# DSDPLC_MCU.net
KiCad netlist of a schematic drawn in Altium Designer
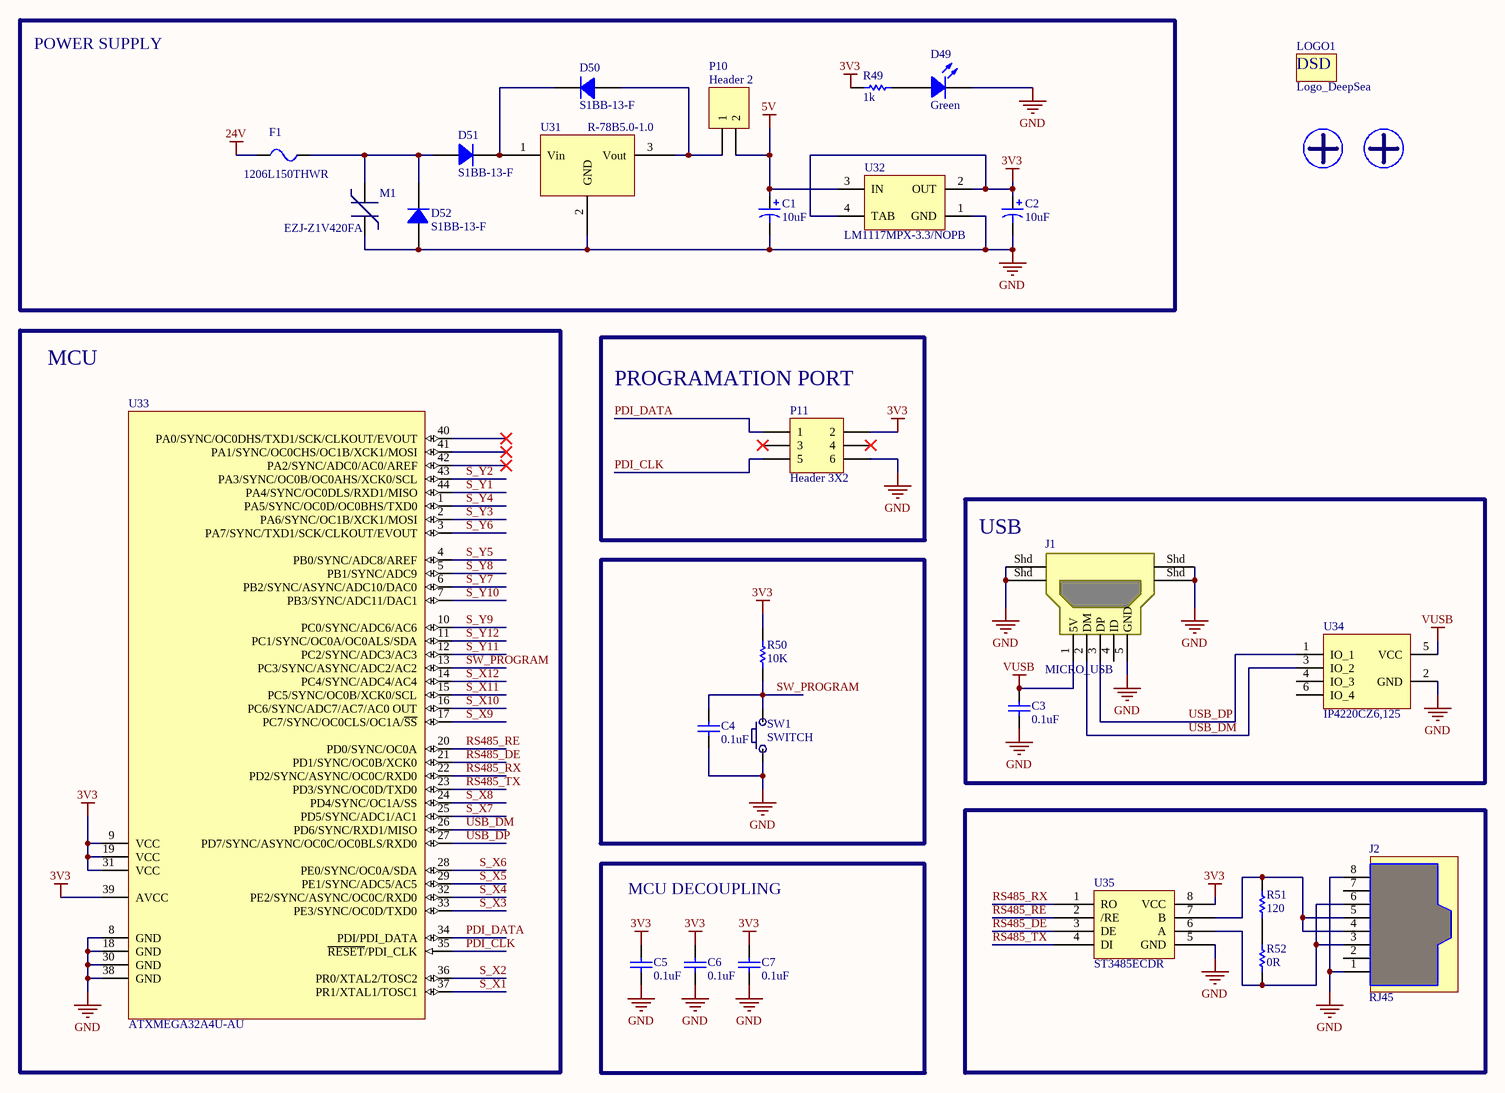
[diagram p0: DSDPLC_MCU.SchDoc]

(export (version "E")
  (design (tool "Eeschema 10.0.6"))
  (components
    (comp (ref "C1") (value "10uF") (footprint "C_TANT_A_3216_N") (libsource (lib "General") (part "CP_SMD")))
    (comp (ref "C2") (value "10uF") (footprint "C_TANT_A_3216_N") (libsource (lib "General") (part "CP_SMD")))
    (comp (ref "C3") (value "0.1uF") (footprint "C0603_N") (libsource (lib "General") (part "C_SMD")))
    (comp (ref "C4") (value "0.1uF") (footprint "C0603_N") (libsource (lib "General") (part "C_SMD")))
    (comp (ref "C5") (value "0.1uF") (footprint "C0603_N") (libsource (lib "General") (part "C_SMD")))
    (comp (ref "C6") (value "0.1uF") (footprint "C0603_N") (libsource (lib "General") (part "C_SMD")))
    (comp (ref "C7") (value "0.1uF") (footprint "C0603_N") (libsource (lib "General") (part "C_SMD")))
    (comp (ref "D49")
      (value "Green")
      (footprint "R0603_N")
      (fields (field (name "COLOR") "Green"))
      (libsource (lib "General") (part "LED_SMD"))
    )
    (comp (ref "D50")
      (value "S1BB-13-F")
      (footprint "SMB_N")
      (description "DIODE GEN PURPOSE 100V 1A SMB")
      (fields (field (name "MANUFACTURER") "Diodes Incorporated"))
      (libsource (lib "General") (part "S1BB-13-F"))
    )
    (comp (ref "D51")
      (value "S1BB-13-F")
      (footprint "SMB_N")
      (description "DIODE GEN PURPOSE 100V 1A SMB")
      (fields (field (name "MANUFACTURER") "Diodes Incorporated"))
      (libsource (lib "General") (part "S1BB-13-F"))
    )
    (comp (ref "D52")
      (value "S1BB-13-F")
      (footprint "SMB_N")
      (description "DIODE GEN PURPOSE 100V 1A SMB")
      (fields (field (name "MANUFACTURER") "Diodes Incorporated"))
      (libsource (lib "General") (part "S1BB-13-F"))
    )
    (comp (ref "F1")
      (value "1206L150THWR")
      (footprint "R1206_N")
      (description "FUSE PTC RESET 8V 1.50A 1206")
      (fields (field (name "MANUFACTURER") "Littelfuse Inc"))
      (libsource (lib "General") (part "1206L150THWR"))
    )
    (comp (ref "J1")
      (value "MICRO_USB")
      (footprint "USB_MICRO_SMD")
      (description "CONN USB MICRO B RECPT SMT R/A")
      (fields (field (name "MANUFACTURER") "FCI") (field (name "MANUFACTURER PART NUMBER") "10118194-0001LF"))
      (libsource (lib "General") (part "MICRO_USB"))
    )
    (comp (ref "J2")
      (value "RJ45")
      (footprint "rj45")
      (description "CONN MOD JACK R/A 8P8C SHIELDED")
      (fields
        (field (name "MANUFACTURER") "TE Connectivity")
        (field (name "MANUFACTURER PART NUMBER") "5555153-1")
      )
      (libsource (lib "General") (part "RJ45"))
    )
    (comp (ref "LOGO1")
      (value "Logo_DeepSea")
      (footprint "DeepSea_logo1")
      (libsource (lib "General") (part "Logo_DeepSea"))
    )
    (comp (ref "M1")
      (value "EZJ-Z1V420FA")
      (footprint "R0603_N")
      (description "VARISTOR 42V 15A 0603")
      (fields (field (name "MANUFACTURER") "Panasonic Electronic Components"))
      (libsource (lib "General") (part "EZJ-Z1V420FA"))
    )
    (comp (ref "M2")
      (value "MountingHole-1/8in")
      (footprint "MoutingHole-1/8in")
      (libsource (lib "General") (part "MountingHole-1/8in"))
    )
    (comp (ref "M3")
      (value "MountingHole-1/8in")
      (footprint "MoutingHole-1/8in")
      (libsource (lib "General") (part "MountingHole-1/8in"))
    )
    (comp (ref "P10")
      (value "Header 2")
      (footprint "HDR1X2")
      (description "Header, 2-Pin")
      (fields (field (name "PUBLISHER") "Altium Limited"))
      (libsource (lib "Miscellaneous Connectors") (part "Header 2"))
    )
    (comp (ref "P11")
      (value "Header 3X2")
      (footprint "HDR2X3")
      (description "Header, 3-Pin, Dual row")
      (fields (field (name "PUBLISHER") "Altium Limited"))
      (libsource (lib "Miscellaneous Connectors") (part "Header 3X2"))
    )
    (comp (ref "R49")
      (value "1k")
      (footprint "R0603_N")
      (fields (field (name "Comment") "R_SMD"))
      (libsource (lib "General") (part "R_SMD"))
    )
    (comp (ref "R50") (value "10K") (footprint "R0603_N") (libsource (lib "discrete") (part "R_SMD")))
    (comp (ref "R51") (value "120") (footprint "R0603_N") (libsource (lib "discrete") (part "R_SMD")))
    (comp (ref "R52") (value "0R") (footprint "R0603_N") (libsource (lib "discrete") (part "R_SMD")))
    (comp (ref "SW1")
      (value "SWITCH")
      (footprint "swich_foot")
      (description "SWITCH TACTILE SPST-NO 0.05A 12V")
      (fields
        (field (name "MANUFACTURER") "TE Connectivity")
        (field (name "MANUFACTURER PART NUMBER") "FSM4JSMATR")
      )
      (libsource (lib "General") (part "SWITCH"))
    )
    (comp (ref "U31")
      (value "R-78B5.0-1.0")
      (footprint "SIP3_RECOM")
      (description "CONV DC/DC 1A 5V OUT SIP VERT")
      (fields (field (name "MANUFACTURER") "Recom Power"))
      (libsource (lib "General") (part "R-78B5.0-1.0"))
    )
    (comp (ref "U32")
      (value "LM1117MPX-3.3/NOPB")
      (footprint "MP04A_N")
      (description "800mA Low-Dropout Linear Regulator, 4-pin SOT-223, Pb-Free")
      (fields
        (field (name "MANUFACTURER") "National Semiconductor")
        (field (name "PUBLISHER") "Altium Limited")
      )
      (libsource (lib "NSC LDO") (part "LM1117MPX-3.3/NOPB"))
    )
    (comp (ref "U33")
      (value "ATXMEGA32A4U-AU")
      (footprint "44A_N")
      (description "IC MCU 8BIT 32KB FLASH 44TQFP")
      (fields (field (name "MANUFACTURER") "Atmel"))
      (libsource (lib "General") (part "ATXMEGA32A4U-AU"))
    )
    (comp (ref "U34")
      (value "IP4220CZ6,125")
      (footprint "SOT457_N")
      (description "IC USB DUAL ESD PROTECT 6TSOP")
      (fields (field (name "MANUFACTURER") "NXP Semiconductors"))
      (libsource (lib "General") (part "IP4220CZ6,125"))
    )
    (comp (ref "U35")
      (value "ST3485ECDR")
      (footprint "SOIC8WA_N")
      (description "TXRX RS485/422 3.3V ESD 8-SOIC")
      (fields (field (name "MANUFACTURER") "STMicroelectronics"))
      (libsource (lib "General") (part "ST3485ECDR"))
    )
  )
  (nets
    (net (code "1") (name "/PDI_CLK") (class "Default")
      (node (ref "P11") (pin "5") (pinfunction "5_5") (pintype "passive"))
      (node (ref "U33") (pin "35") (pinfunction "~{RESET}/PDI_CLK_35") (pintype "input"))
    )
    (net (code "2") (name "/PDI_DATA") (class "Default")
      (node (ref "P11") (pin "1") (pinfunction "1_1") (pintype "passive"))
      (node (ref "U33") (pin "34") (pinfunction "PDI/PDI_DATA_34") (pintype "bidirectional"))
    )
    (net (code "3") (name "/RS485_DE") (class "Default")
      (node (ref "U33") (pin "21") (pinfunction "PD1/SYNC/OC0B/XCK0_21") (pintype "bidirectional"))
      (node (ref "U35") (pin "3") (pinfunction "DE_3") (pintype "passive"))
    )
    (net (code "4") (name "/RS485_RE") (class "Default")
      (node (ref "U33") (pin "20") (pinfunction "PD0/SYNC/OC0A_20") (pintype "bidirectional"))
      (node (ref "U35") (pin "2") (pinfunction "/RE_2") (pintype "passive"))
    )
    (net (code "5") (name "/RS485_RX") (class "Default")
      (node (ref "U33") (pin "22") (pinfunction "PD2/SYNC/ASYNC/OC0C/RXD0_22") (pintype "bidirectional"))
      (node (ref "U35") (pin "1") (pinfunction "RO_1") (pintype "passive"))
    )
    (net (code "6") (name "/RS485_TX") (class "Default")
      (node (ref "U33") (pin "23") (pinfunction "PD3/SYNC/OC0D/TXD0_23") (pintype "bidirectional"))
      (node (ref "U35") (pin "4") (pinfunction "DI_4") (pintype "passive"))
    )
    (net (code "7") (name "/SW_PROGRAM") (class "Default")
      (node (ref "C4") (pin "1") (pinfunction "1_1") (pintype "passive"))
      (node (ref "R50") (pin "1") (pinfunction "1_1") (pintype "passive"))
      (node (ref "SW1") (pin "2") (pinfunction "*_2") (pintype "passive"))
      (node (ref "U33") (pin "13") (pinfunction "PC3/SYNC/ASYNC/ADC2/AC2_13") (pintype "bidirectional"))
    )
    (net (code "8") (name "/S_X1") (class "Default")
      (node (ref "U33") (pin "37") (pinfunction "PR1/XTAL1/TOSC1_37") (pintype "bidirectional"))
    )
    (net (code "9") (name "/S_X2") (class "Default")
      (node (ref "U33") (pin "36") (pinfunction "PR0/XTAL2/TOSC2_36") (pintype "bidirectional"))
    )
    (net (code "10") (name "/S_X3") (class "Default")
      (node (ref "U33") (pin "33") (pinfunction "PE3/SYNC/OC0D/TXD0_33") (pintype "bidirectional"))
    )
    (net (code "11") (name "/S_X4") (class "Default")
      (node (ref "U33") (pin "32") (pinfunction "PE2/SYNC/ASYNC/OC0C/RXD0_32") (pintype "bidirectional"))
    )
    (net (code "12") (name "/S_X5") (class "Default")
      (node (ref "U33") (pin "29") (pinfunction "PE1/SYNC/ADC5/AC5_29") (pintype "bidirectional"))
    )
    (net (code "13") (name "/S_X6") (class "Default")
      (node (ref "U33") (pin "28") (pinfunction "PE0/SYNC/OC0A/SDA_28") (pintype "bidirectional"))
    )
    (net (code "14") (name "/S_X7") (class "Default")
      (node (ref "U33") (pin "25") (pinfunction "PD5/SYNC/ADC1/AC1_25") (pintype "bidirectional"))
    )
    (net (code "15") (name "/S_X8") (class "Default")
      (node (ref "U33") (pin "24") (pinfunction "PD4/SYNC/OC1A/SS_24") (pintype "bidirectional"))
    )
    (net (code "16") (name "/S_X9") (class "Default")
      (node (ref "U33") (pin "17") (pinfunction "PC7/SYNC/OC0CLS/OC1A/~{SS}_17") (pintype "bidirectional"))
    )
    (net (code "17") (name "/S_X10") (class "Default")
      (node (ref "U33") (pin "16") (pinfunction "PC6/SYNC/ADC7/AC7/AC0_OUT_16") (pintype "bidirectional"))
    )
    (net (code "18") (name "/S_X11") (class "Default")
      (node (ref "U33") (pin "15") (pinfunction "PC5/SYNC/OC0B/XCK0/SCL_15") (pintype "bidirectional"))
    )
    (net (code "19") (name "/S_X12") (class "Default")
      (node (ref "U33") (pin "14") (pinfunction "PC4/SYNC/ADC4/AC4_14") (pintype "bidirectional"))
    )
    (net (code "20") (name "/S_Y1") (class "Default")
      (node (ref "U33") (pin "44") (pinfunction "PA4/SYNC/OC0DLS/RXD1/MISO_44") (pintype "bidirectional"))
    )
    (net (code "21") (name "/S_Y2") (class "Default")
      (node (ref "U33") (pin "43") (pinfunction "PA3/SYNC/OC0B/OC0AHS/XCK0/SCL_43") (pintype "bidirectional"))
    )
    (net (code "22") (name "/S_Y3") (class "Default")
      (node (ref "U33") (pin "2") (pinfunction "PA6/SYNC/OC1B/XCK1/MOSI_2") (pintype "bidirectional"))
    )
    (net (code "23") (name "/S_Y4") (class "Default")
      (node (ref "U33") (pin "1") (pinfunction "PA5/SYNC/OC0D/OC0BHS/TXD0_1") (pintype "bidirectional"))
    )
    (net (code "24") (name "/S_Y5") (class "Default")
      (node (ref "U33") (pin "4") (pinfunction "PB0/SYNC/ADC8/AREF_4") (pintype "bidirectional"))
    )
    (net (code "25") (name "/S_Y6") (class "Default")
      (node (ref "U33") (pin "3") (pinfunction "PA7/SYNC/TXD1/SCK/CLKOUT/EVOUT_3") (pintype "bidirectional"))
    )
    (net (code "26") (name "/S_Y7") (class "Default")
      (node (ref "U33") (pin "6") (pinfunction "PB2/SYNC/ASYNC/ADC10/DAC0_6") (pintype "bidirectional"))
    )
    (net (code "27") (name "/S_Y8") (class "Default")
      (node (ref "U33") (pin "5") (pinfunction "PB1/SYNC/ADC9_5") (pintype "bidirectional"))
    )
    (net (code "28") (name "/S_Y9") (class "Default")
      (node (ref "U33") (pin "10") (pinfunction "PC0/SYNC/ADC6/AC6_10") (pintype "bidirectional"))
    )
    (net (code "29") (name "/S_Y10") (class "Default")
      (node (ref "U33") (pin "7") (pinfunction "PB3/SYNC/ADC11/DAC1_7") (pintype "bidirectional"))
    )
    (net (code "30") (name "/S_Y11") (class "Default")
      (node (ref "U33") (pin "12") (pinfunction "PC2/SYNC/ADC3/AC3_12") (pintype "bidirectional"))
    )
    (net (code "31") (name "/S_Y12") (class "Default")
      (node (ref "U33") (pin "11") (pinfunction "PC1/SYNC/OC0A/OC0ALS/SDA_11") (pintype "bidirectional"))
    )
    (net (code "32") (name "/USB_DM") (class "Default")
      (node (ref "J1") (pin "2") (pinfunction "DM_2") (pintype "passive"))
      (node (ref "U33") (pin "26") (pinfunction "PD6/SYNC/RXD1/MISO_26") (pintype "bidirectional"))
      (node (ref "U34") (pin "3") (pinfunction "IO_2_3") (pintype "passive"))
    )
    (net (code "33") (name "/USB_DP") (class "Default")
      (node (ref "J1") (pin "3") (pinfunction "DP_3") (pintype "passive"))
      (node (ref "U33") (pin "27") (pinfunction "PD7/SYNC/ASYNC/OC0C/OC0BLS/RXD0_27") (pintype "bidirectional"))
      (node (ref "U34") (pin "1") (pinfunction "IO_1_1") (pintype "passive"))
    )
    (net (code "34") (name "3V3") (class "Default")
      (node (ref "C2") (pin "1") (pinfunction "1_1") (pintype "passive"))
      (node (ref "C5") (pin "2") (pinfunction "2_2") (pintype "passive"))
      (node (ref "C6") (pin "2") (pinfunction "2_2") (pintype "passive"))
      (node (ref "C7") (pin "2") (pinfunction "2_2") (pintype "passive"))
      (node (ref "P11") (pin "2") (pinfunction "2_2") (pintype "passive"))
      (node (ref "R49") (pin "1") (pinfunction "1_1") (pintype "passive"))
      (node (ref "R50") (pin "2") (pinfunction "2_2") (pintype "passive"))
      (node (ref "U32") (pin "2") (pinfunction "OUT_2") (pintype "power_in"))
      (node (ref "U32") (pin "4") (pinfunction "TAB_4") (pintype "power_in"))
      (node (ref "U33") (pin "19") (pinfunction "VCC_19") (pintype "power_in"))
      (node (ref "U33") (pin "31") (pinfunction "VCC_31") (pintype "power_in"))
      (node (ref "U33") (pin "39") (pinfunction "AVCC_39") (pintype "power_in"))
      (node (ref "U33") (pin "9") (pinfunction "VCC_9") (pintype "power_in"))
      (node (ref "U35") (pin "8") (pinfunction "VCC_8") (pintype "passive"))
    )
    (net (code "35") (name "5V") (class "Default")
      (node (ref "C1") (pin "1") (pinfunction "1_1") (pintype "passive"))
      (node (ref "P10") (pin "2") (pinfunction "2_2") (pintype "passive"))
      (node (ref "U32") (pin "3") (pinfunction "IN_3") (pintype "power_in"))
    )
    (net (code "36") (name "24V") (class "Default") (node (ref "F1") (pin "1") (pintype "passive")))
    (net (code "37") (name "GND") (class "Default")
      (node (ref "C1") (pin "2") (pinfunction "2_2") (pintype "passive"))
      (node (ref "C2") (pin "2") (pinfunction "2_2") (pintype "passive"))
      (node (ref "C3") (pin "1") (pinfunction "1_1") (pintype "passive"))
      (node (ref "C4") (pin "2") (pinfunction "2_2") (pintype "passive"))
      (node (ref "C5") (pin "1") (pinfunction "1_1") (pintype "passive"))
      (node (ref "C6") (pin "1") (pinfunction "1_1") (pintype "passive"))
      (node (ref "C7") (pin "1") (pinfunction "1_1") (pintype "passive"))
      (node (ref "D49") (pin "2") (pinfunction "K_2") (pintype "passive"))
      (node (ref "D52") (pin "1") (pinfunction "A_1") (pintype "passive"))
      (node (ref "J1") (pin "5") (pinfunction "GND_5") (pintype "power_in"))
      (node (ref "J1") (pin "Shd") (pinfunction "6_Shd") (pintype "passive"))
      (node (ref "J2") (pin "1") (pintype "passive"))
      (node (ref "J2") (pin "8") (pintype "passive"))
      (node (ref "M1") (pin "2") (pintype "passive"))
      (node (ref "P11") (pin "6") (pinfunction "6_6") (pintype "passive"))
      (node (ref "SW1") (pin "1") (pinfunction "*_1") (pintype "passive"))
      (node (ref "U31") (pin "2") (pinfunction "GND_2") (pintype "passive"))
      (node (ref "U32") (pin "1") (pinfunction "GND_1") (pintype "power_in"))
      (node (ref "U33") (pin "18") (pinfunction "GND_18") (pintype "power_in"))
      (node (ref "U33") (pin "30") (pinfunction "GND_30") (pintype "power_in"))
      (node (ref "U33") (pin "38") (pinfunction "GND_38") (pintype "power_in"))
      (node (ref "U33") (pin "8") (pinfunction "GND_8") (pintype "power_in"))
      (node (ref "U34") (pin "2") (pinfunction "GND_2") (pintype "passive"))
      (node (ref "U35") (pin "5") (pinfunction "GND_5") (pintype "passive"))
    )
    (net (code "38") (name "Net-(D49-A)") (class "Default")
      (node (ref "D49") (pin "1") (pinfunction "A_1") (pintype "passive"))
      (node (ref "R49") (pin "2") (pinfunction "2_2") (pintype "passive"))
    )
    (net (code "39") (name "Net-(D50-A)") (class "Default")
      (node (ref "D50") (pin "1") (pinfunction "A_1") (pintype "passive"))
      (node (ref "P10") (pin "1") (pinfunction "1_1") (pintype "passive"))
      (node (ref "U31") (pin "3") (pinfunction "Vout_3") (pintype "passive"))
    )
    (net (code "40") (name "Net-(D50-K)") (class "Default")
      (node (ref "D50") (pin "2") (pinfunction "K_2") (pintype "passive"))
      (node (ref "D51") (pin "2") (pinfunction "K_2") (pintype "passive"))
      (node (ref "U31") (pin "1") (pinfunction "Vin_1") (pintype "passive"))
    )
    (net (code "41") (name "Net-(D51-A)") (class "Default")
      (node (ref "D51") (pin "1") (pinfunction "A_1") (pintype "passive"))
      (node (ref "D52") (pin "2") (pinfunction "K_2") (pintype "passive"))
      (node (ref "F1") (pin "2") (pintype "passive"))
      (node (ref "M1") (pin "1") (pintype "passive"))
    )
    (net (code "42") (name "Net-(R51-Pad1)") (class "Default")
      (node (ref "R51") (pin "1") (pinfunction "1_1") (pintype "passive"))
      (node (ref "R52") (pin "2") (pinfunction "2_2") (pintype "passive"))
    )
    (net (code "43") (name "Net-(U35-A)") (class "Default")
      (node (ref "J2") (pin "3") (pintype "passive"))
      (node (ref "J2") (pin "6") (pintype "passive"))
      (node (ref "R52") (pin "1") (pinfunction "1_1") (pintype "passive"))
      (node (ref "U35") (pin "6") (pinfunction "A_6") (pintype "passive"))
    )
    (net (code "44") (name "Net-(U35-B)") (class "Default")
      (node (ref "J2") (pin "4") (pintype "passive"))
      (node (ref "J2") (pin "5") (pintype "passive"))
      (node (ref "R51") (pin "2") (pinfunction "2_2") (pintype "passive"))
      (node (ref "U35") (pin "7") (pinfunction "B_7") (pintype "passive"))
    )
    (net (code "45") (name "VUSB") (class "Default")
      (node (ref "C3") (pin "2") (pinfunction "2_2") (pintype "passive"))
      (node (ref "J1") (pin "1") (pinfunction "5V_1") (pintype "power_in"))
      (node (ref "U34") (pin "5") (pinfunction "VCC_5") (pintype "passive"))
    )
    (net (code "46") (name "unconnected-(J1-ID-Pad4)") (class "Default")
      (node (ref "J1") (pin "4") (pinfunction "ID_4") (pintype "passive"))
    )
    (net (code "47") (name "unconnected-(J2-Pad2)") (class "Default")
      (node (ref "J2") (pin "2") (pintype "passive"))
    )
    (net (code "48") (name "unconnected-(J2-Pad7)") (class "Default")
      (node (ref "J2") (pin "7") (pintype "passive"))
    )
    (net (code "49") (name "unconnected-(P11-Pad3)") (class "Default")
      (node (ref "P11") (pin "3") (pinfunction "3_3") (pintype "passive+no_connect"))
    )
    (net (code "50") (name "unconnected-(P11-Pad4)") (class "Default")
      (node (ref "P11") (pin "4") (pinfunction "4_4") (pintype "passive+no_connect"))
    )
    (net (code "51") (name "unconnected-(U33-PA0{slash}SYNC{slash}OC0DHS{slash}TXD1{slash}SCK{slash}CLKOUT{slash}EVOUT-Pad40)") (class "Default")
      (node (ref "U33") (pin "40") (pinfunction "PA0/SYNC/OC0DHS/TXD1/SCK/CLKOUT/EVOUT_40") (pintype "bidirectional+no_connect"))
    )
    (net (code "52") (name "unconnected-(U33-PA1{slash}SYNC{slash}OC0CHS{slash}OC1B{slash}XCK1{slash}MOSI-Pad41)") (class "Default")
      (node (ref "U33") (pin "41") (pinfunction "PA1/SYNC/OC0CHS/OC1B/XCK1/MOSI_41") (pintype "bidirectional+no_connect"))
    )
    (net (code "53") (name "unconnected-(U33-PA2{slash}SYNC{slash}ADC0{slash}AC0{slash}AREF-Pad42)") (class "Default")
      (node (ref "U33") (pin "42") (pinfunction "PA2/SYNC/ADC0/AC0/AREF_42") (pintype "bidirectional+no_connect"))
    )
    (net (code "54") (name "unconnected-(U34-IO_3-Pad4)") (class "Default")
      (node (ref "U34") (pin "4") (pinfunction "IO_3_4") (pintype "passive"))
    )
    (net (code "55") (name "unconnected-(U34-IO_4-Pad6)") (class "Default")
      (node (ref "U34") (pin "6") (pinfunction "IO_4_6") (pintype "passive"))
    )
  )
)
